# PortExpander.net
KiCad netlist of a schematic drawn in EAGLE
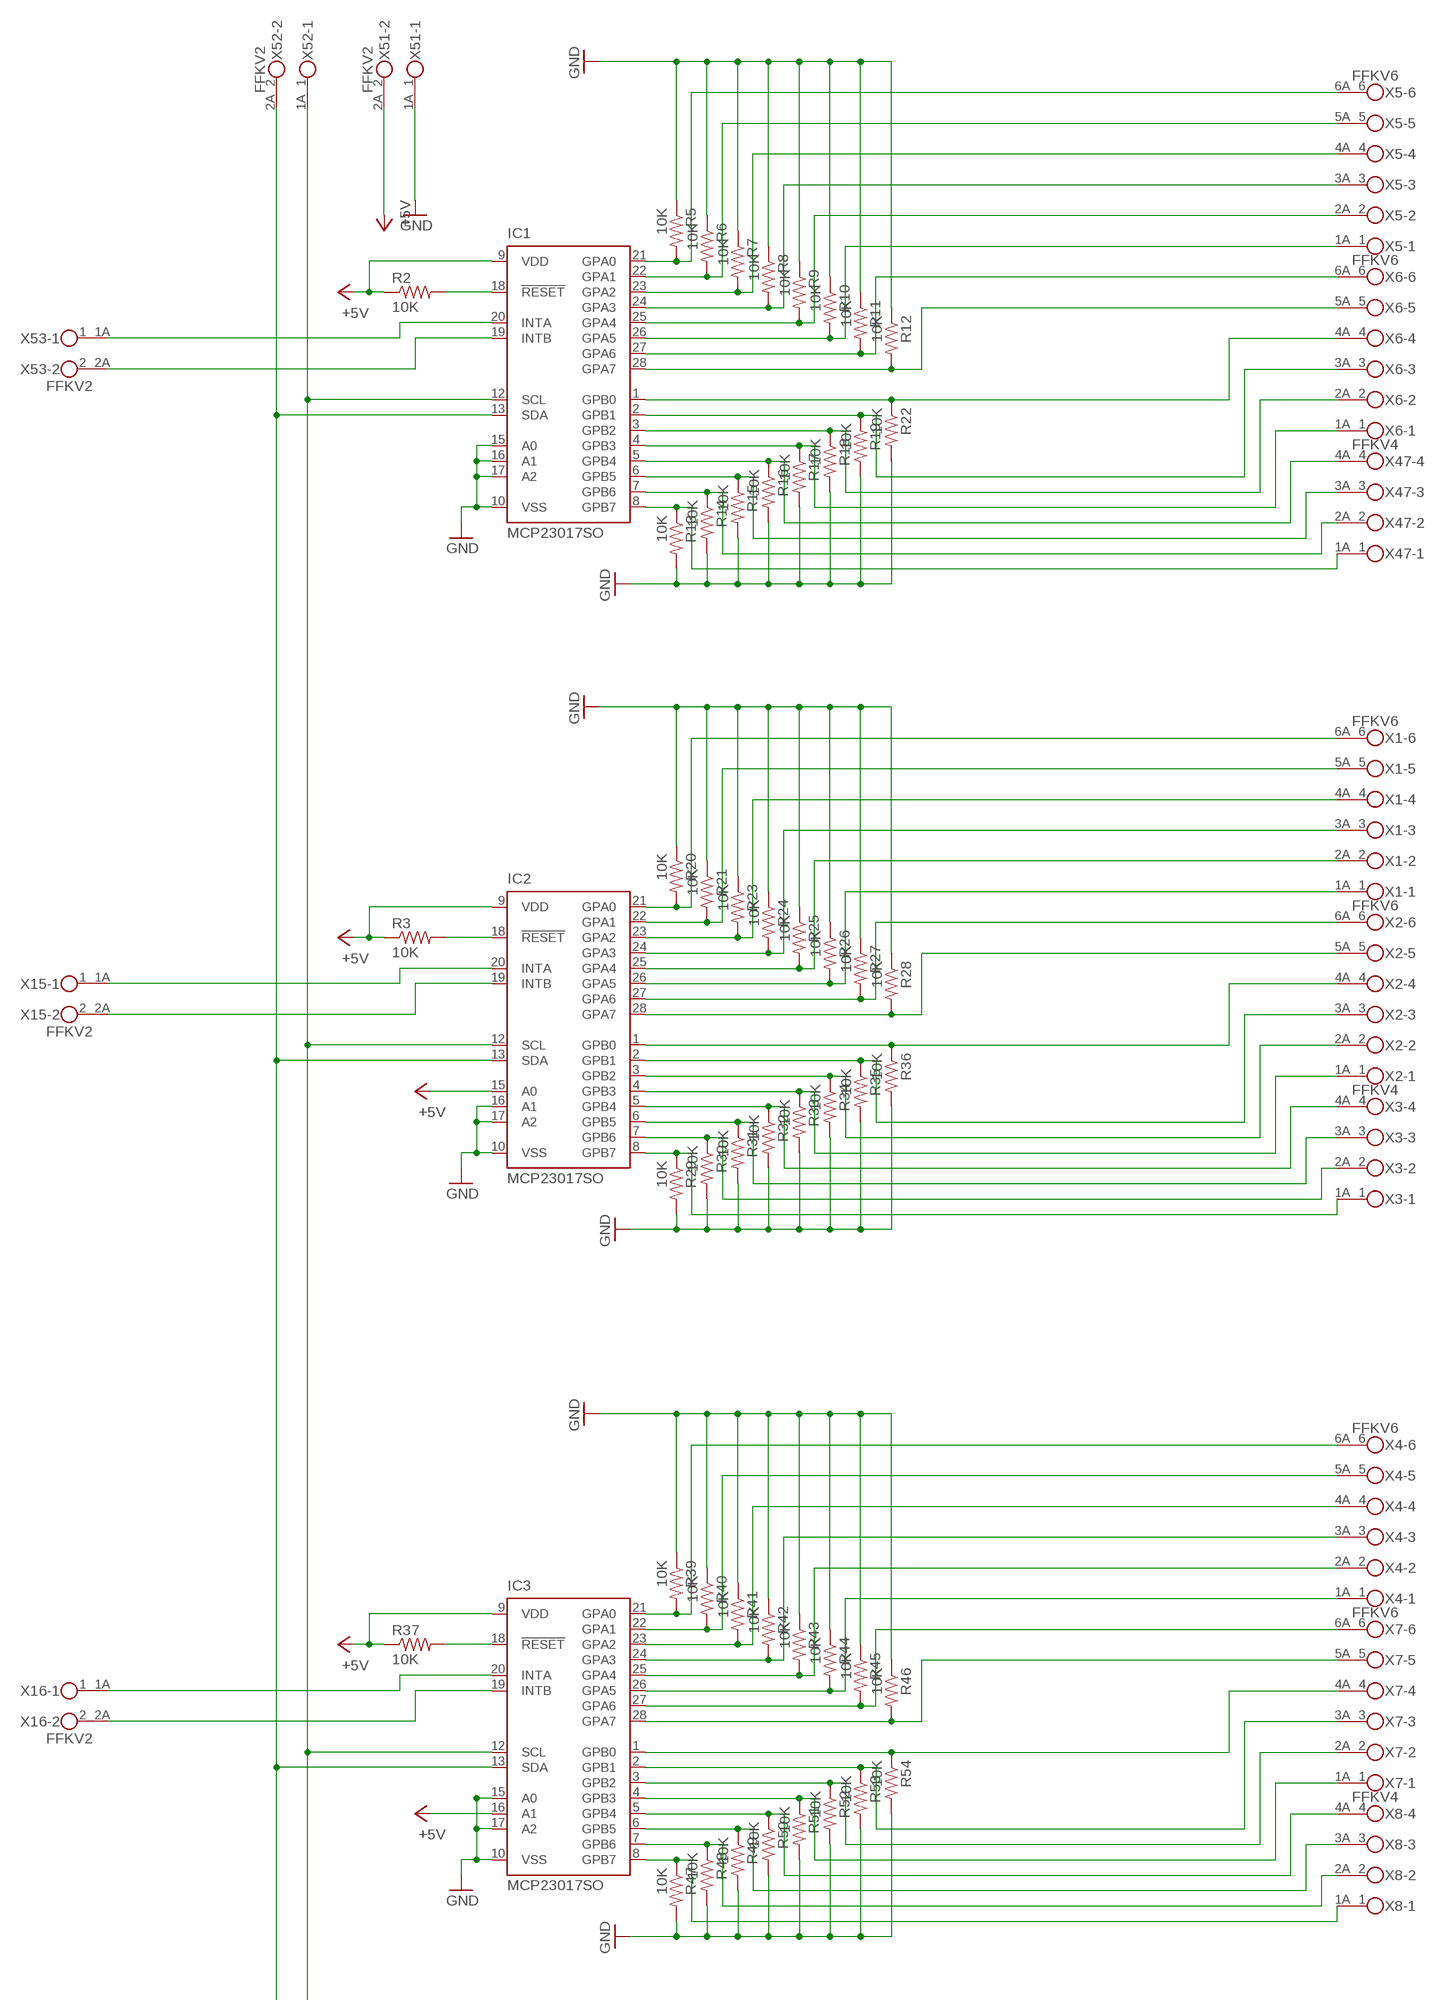
[diagram p0: schematic, sheet 1, part 1 of 2]
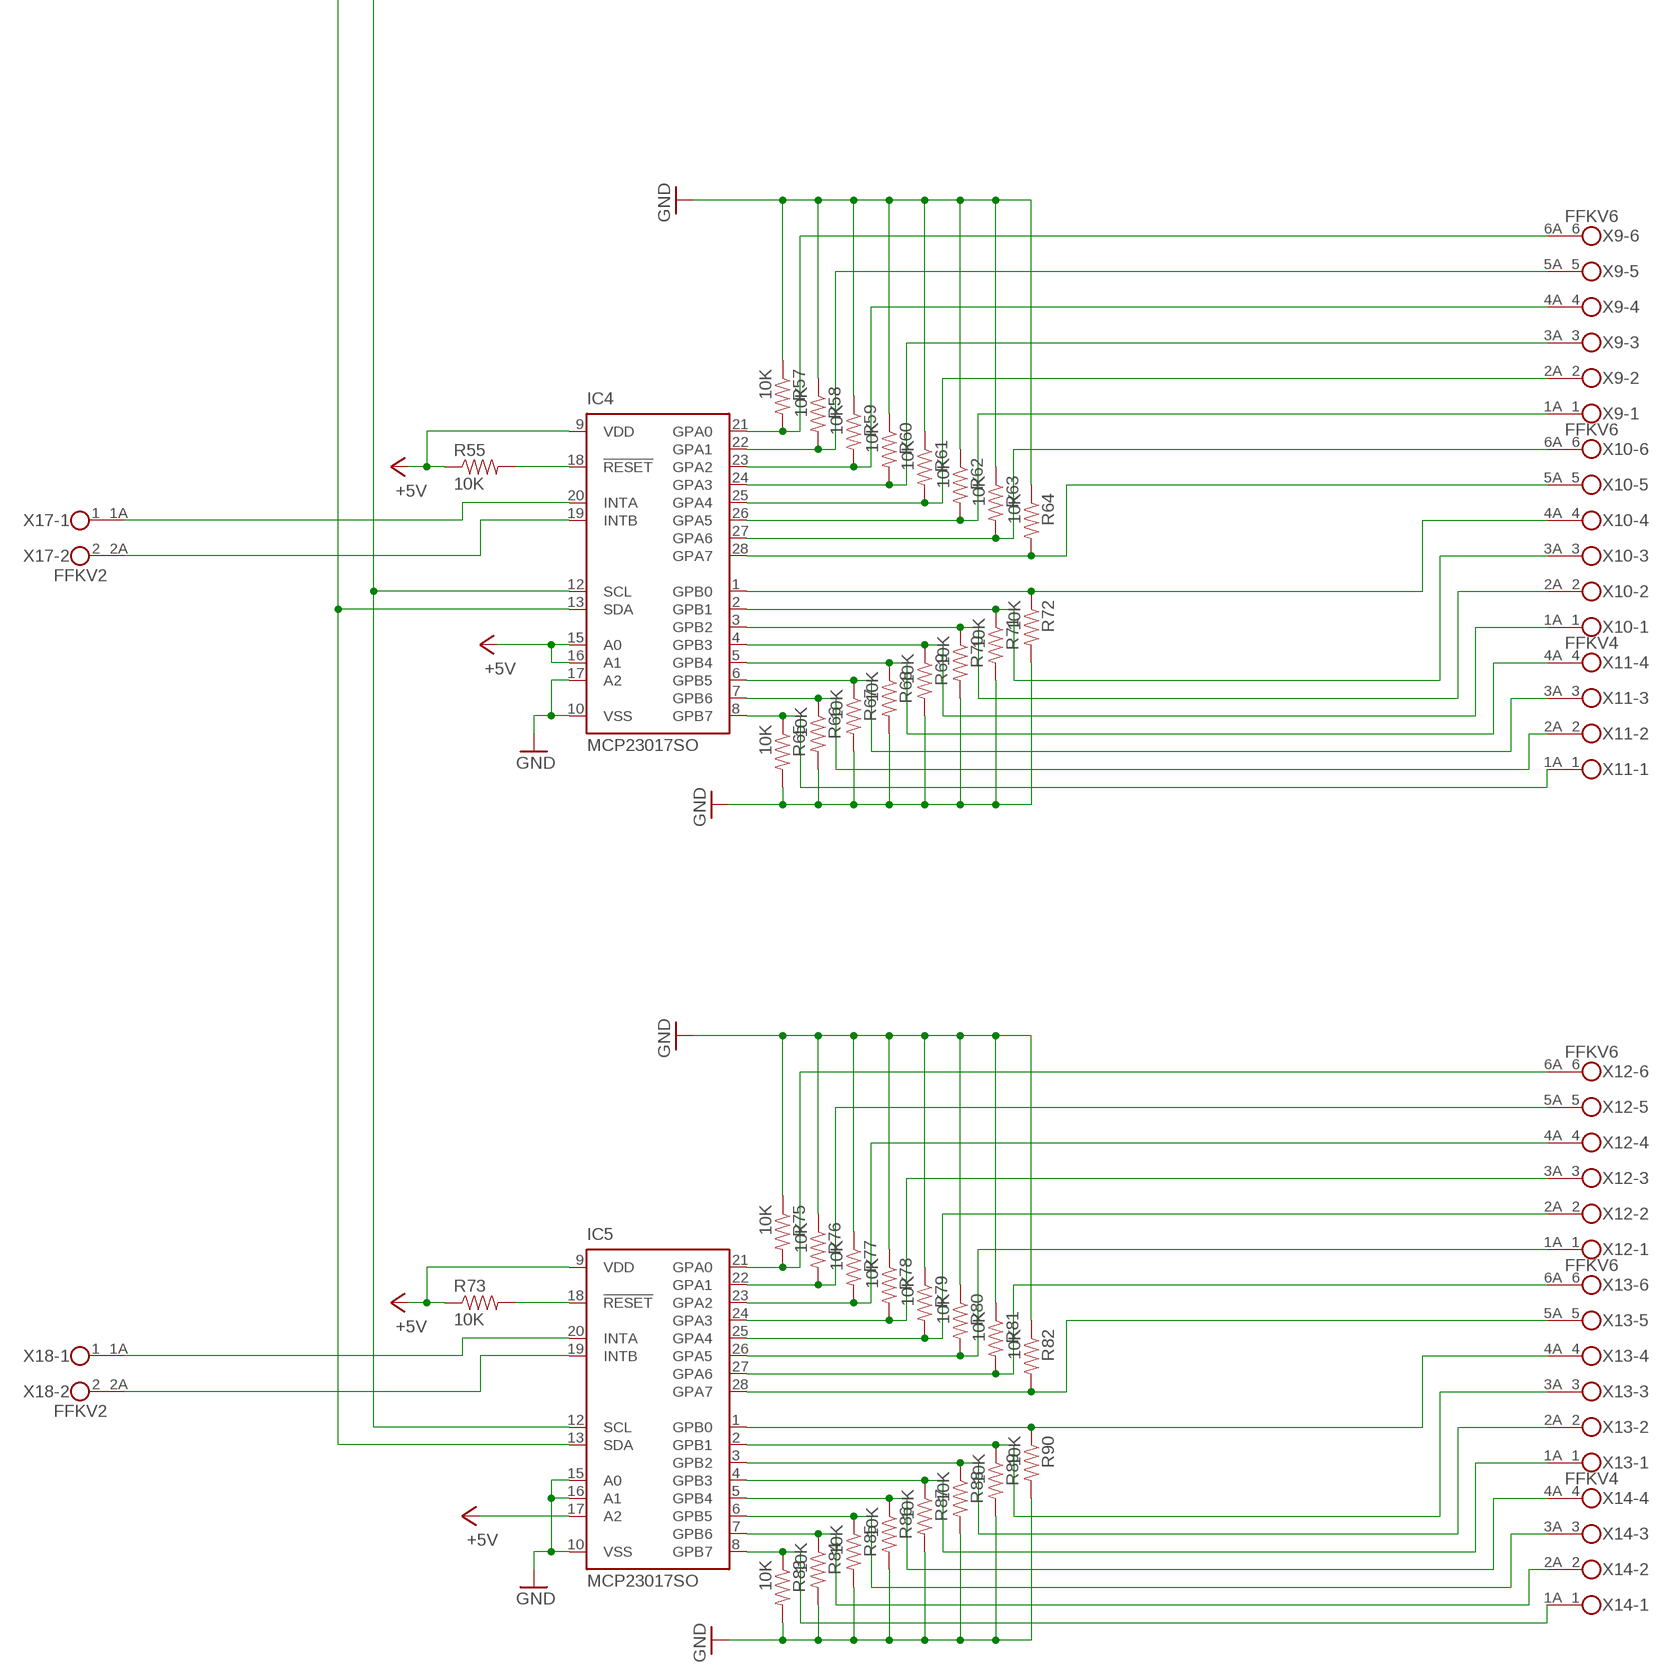
[diagram p1: schematic, sheet 1, part 2 of 2]

(export (version "E")
  (design (tool "Eeschema 10.0.6"))
  (components
    (comp (ref "IC1")
      (value "MCP23017SO")
      (footprint "eagle-import:SO28W")
      (fields (field (name "MF") "MICROCHIP") (field (name "MPN") "MCP23017-E/SO"))
      (libsource (lib "eagle-import") (part "MCP23017SO"))
    )
    (comp (ref "IC2")
      (value "MCP23017SO")
      (footprint "eagle-import:SO28W")
      (fields (field (name "MF") "MICROCHIP") (field (name "MPN") "MCP23017-E/SO"))
      (libsource (lib "eagle-import") (part "MCP23017SO"))
    )
    (comp (ref "IC3")
      (value "MCP23017SO")
      (footprint "eagle-import:SO28W")
      (fields (field (name "MF") "MICROCHIP") (field (name "MPN") "MCP23017-E/SO"))
      (libsource (lib "eagle-import") (part "MCP23017SO"))
    )
    (comp (ref "IC4")
      (value "MCP23017SO")
      (footprint "eagle-import:SO28W")
      (fields (field (name "MF") "MICROCHIP") (field (name "MPN") "MCP23017-E/SO"))
      (libsource (lib "eagle-import") (part "MCP23017SO"))
    )
    (comp (ref "IC5")
      (value "MCP23017SO")
      (footprint "eagle-import:SO28W")
      (fields (field (name "MF") "MICROCHIP") (field (name "MPN") "MCP23017-E/SO"))
      (libsource (lib "eagle-import") (part "MCP23017SO"))
    )
    (comp (ref "R2")
      (value "10K")
      (footprint "eagle-import:1206")
      (libsource (lib "eagle-import") (part "RESISTOR1206"))
    )
    (comp (ref "R3")
      (value "10K")
      (footprint "eagle-import:1206")
      (libsource (lib "eagle-import") (part "RESISTOR1206"))
    )
    (comp (ref "R5")
      (value "10K")
      (footprint "eagle-import:1206")
      (libsource (lib "eagle-import") (part "RESISTOR1206"))
    )
    (comp (ref "R6")
      (value "10K")
      (footprint "eagle-import:1206")
      (libsource (lib "eagle-import") (part "RESISTOR1206"))
    )
    (comp (ref "R7")
      (value "10K")
      (footprint "eagle-import:1206")
      (libsource (lib "eagle-import") (part "RESISTOR1206"))
    )
    (comp (ref "R8")
      (value "10K")
      (footprint "eagle-import:1206")
      (libsource (lib "eagle-import") (part "RESISTOR1206"))
    )
    (comp (ref "R9")
      (value "10K")
      (footprint "eagle-import:1206")
      (libsource (lib "eagle-import") (part "RESISTOR1206"))
    )
    (comp (ref "R10")
      (value "10K")
      (footprint "eagle-import:1206")
      (libsource (lib "eagle-import") (part "RESISTOR1206"))
    )
    (comp (ref "R11")
      (value "10K")
      (footprint "eagle-import:1206")
      (libsource (lib "eagle-import") (part "RESISTOR1206"))
    )
    (comp (ref "R12")
      (value "10K")
      (footprint "eagle-import:1206")
      (libsource (lib "eagle-import") (part "RESISTOR1206"))
    )
    (comp (ref "R13")
      (value "10K")
      (footprint "eagle-import:1206")
      (libsource (lib "eagle-import") (part "RESISTOR1206"))
    )
    (comp (ref "R14")
      (value "10K")
      (footprint "eagle-import:1206")
      (libsource (lib "eagle-import") (part "RESISTOR1206"))
    )
    (comp (ref "R15")
      (value "10K")
      (footprint "eagle-import:1206")
      (libsource (lib "eagle-import") (part "RESISTOR1206"))
    )
    (comp (ref "R16")
      (value "10K")
      (footprint "eagle-import:1206")
      (libsource (lib "eagle-import") (part "RESISTOR1206"))
    )
    (comp (ref "R17")
      (value "10K")
      (footprint "eagle-import:1206")
      (libsource (lib "eagle-import") (part "RESISTOR1206"))
    )
    (comp (ref "R18")
      (value "10K")
      (footprint "eagle-import:1206")
      (libsource (lib "eagle-import") (part "RESISTOR1206"))
    )
    (comp (ref "R19")
      (value "10K")
      (footprint "eagle-import:1206")
      (libsource (lib "eagle-import") (part "RESISTOR1206"))
    )
    (comp (ref "R20")
      (value "10K")
      (footprint "eagle-import:1206")
      (libsource (lib "eagle-import") (part "RESISTOR1206"))
    )
    (comp (ref "R21")
      (value "10K")
      (footprint "eagle-import:1206")
      (libsource (lib "eagle-import") (part "RESISTOR1206"))
    )
    (comp (ref "R22")
      (value "10K")
      (footprint "eagle-import:1206")
      (libsource (lib "eagle-import") (part "RESISTOR1206"))
    )
    (comp (ref "R23")
      (value "10K")
      (footprint "eagle-import:1206")
      (libsource (lib "eagle-import") (part "RESISTOR1206"))
    )
    (comp (ref "R24")
      (value "10K")
      (footprint "eagle-import:1206")
      (libsource (lib "eagle-import") (part "RESISTOR1206"))
    )
    (comp (ref "R25")
      (value "10K")
      (footprint "eagle-import:1206")
      (libsource (lib "eagle-import") (part "RESISTOR1206"))
    )
    (comp (ref "R26")
      (value "10K")
      (footprint "eagle-import:1206")
      (libsource (lib "eagle-import") (part "RESISTOR1206"))
    )
    (comp (ref "R27")
      (value "10K")
      (footprint "eagle-import:1206")
      (libsource (lib "eagle-import") (part "RESISTOR1206"))
    )
    (comp (ref "R28")
      (value "10K")
      (footprint "eagle-import:1206")
      (libsource (lib "eagle-import") (part "RESISTOR1206"))
    )
    (comp (ref "R29")
      (value "10K")
      (footprint "eagle-import:1206")
      (libsource (lib "eagle-import") (part "RESISTOR1206"))
    )
    (comp (ref "R30")
      (value "10K")
      (footprint "eagle-import:1206")
      (libsource (lib "eagle-import") (part "RESISTOR1206"))
    )
    (comp (ref "R31")
      (value "10K")
      (footprint "eagle-import:1206")
      (libsource (lib "eagle-import") (part "RESISTOR1206"))
    )
    (comp (ref "R32")
      (value "10K")
      (footprint "eagle-import:1206")
      (libsource (lib "eagle-import") (part "RESISTOR1206"))
    )
    (comp (ref "R33")
      (value "10K")
      (footprint "eagle-import:1206")
      (libsource (lib "eagle-import") (part "RESISTOR1206"))
    )
    (comp (ref "R34")
      (value "10K")
      (footprint "eagle-import:1206")
      (libsource (lib "eagle-import") (part "RESISTOR1206"))
    )
    (comp (ref "R35")
      (value "10K")
      (footprint "eagle-import:1206")
      (libsource (lib "eagle-import") (part "RESISTOR1206"))
    )
    (comp (ref "R36")
      (value "10K")
      (footprint "eagle-import:1206")
      (libsource (lib "eagle-import") (part "RESISTOR1206"))
    )
    (comp (ref "R37")
      (value "10K")
      (footprint "eagle-import:1206")
      (libsource (lib "eagle-import") (part "RESISTOR1206"))
    )
    (comp (ref "R39")
      (value "10K")
      (footprint "eagle-import:1206")
      (libsource (lib "eagle-import") (part "RESISTOR1206"))
    )
    (comp (ref "R40")
      (value "10K")
      (footprint "eagle-import:1206")
      (libsource (lib "eagle-import") (part "RESISTOR1206"))
    )
    (comp (ref "R41")
      (value "10K")
      (footprint "eagle-import:1206")
      (libsource (lib "eagle-import") (part "RESISTOR1206"))
    )
    (comp (ref "R42")
      (value "10K")
      (footprint "eagle-import:1206")
      (libsource (lib "eagle-import") (part "RESISTOR1206"))
    )
    (comp (ref "R43")
      (value "10K")
      (footprint "eagle-import:1206")
      (libsource (lib "eagle-import") (part "RESISTOR1206"))
    )
    (comp (ref "R44")
      (value "10K")
      (footprint "eagle-import:1206")
      (libsource (lib "eagle-import") (part "RESISTOR1206"))
    )
    (comp (ref "R45")
      (value "10K")
      (footprint "eagle-import:1206")
      (libsource (lib "eagle-import") (part "RESISTOR1206"))
    )
    (comp (ref "R46")
      (value "10K")
      (footprint "eagle-import:1206")
      (libsource (lib "eagle-import") (part "RESISTOR1206"))
    )
    (comp (ref "R47")
      (value "10K")
      (footprint "eagle-import:1206")
      (libsource (lib "eagle-import") (part "RESISTOR1206"))
    )
    (comp (ref "R48")
      (value "10K")
      (footprint "eagle-import:1206")
      (libsource (lib "eagle-import") (part "RESISTOR1206"))
    )
    (comp (ref "R49")
      (value "10K")
      (footprint "eagle-import:1206")
      (libsource (lib "eagle-import") (part "RESISTOR1206"))
    )
    (comp (ref "R50")
      (value "10K")
      (footprint "eagle-import:1206")
      (libsource (lib "eagle-import") (part "RESISTOR1206"))
    )
    (comp (ref "R51")
      (value "10K")
      (footprint "eagle-import:1206")
      (libsource (lib "eagle-import") (part "RESISTOR1206"))
    )
    (comp (ref "R52")
      (value "10K")
      (footprint "eagle-import:1206")
      (libsource (lib "eagle-import") (part "RESISTOR1206"))
    )
    (comp (ref "R53")
      (value "10K")
      (footprint "eagle-import:1206")
      (libsource (lib "eagle-import") (part "RESISTOR1206"))
    )
    (comp (ref "R54")
      (value "10K")
      (footprint "eagle-import:1206")
      (libsource (lib "eagle-import") (part "RESISTOR1206"))
    )
    (comp (ref "R55")
      (value "10K")
      (footprint "eagle-import:1206")
      (libsource (lib "eagle-import") (part "RESISTOR1206"))
    )
    (comp (ref "R57")
      (value "10K")
      (footprint "eagle-import:1206")
      (libsource (lib "eagle-import") (part "RESISTOR1206"))
    )
    (comp (ref "R58")
      (value "10K")
      (footprint "eagle-import:1206")
      (libsource (lib "eagle-import") (part "RESISTOR1206"))
    )
    (comp (ref "R59")
      (value "10K")
      (footprint "eagle-import:1206")
      (libsource (lib "eagle-import") (part "RESISTOR1206"))
    )
    (comp (ref "R60")
      (value "10K")
      (footprint "eagle-import:1206")
      (libsource (lib "eagle-import") (part "RESISTOR1206"))
    )
    (comp (ref "R61")
      (value "10K")
      (footprint "eagle-import:1206")
      (libsource (lib "eagle-import") (part "RESISTOR1206"))
    )
    (comp (ref "R62")
      (value "10K")
      (footprint "eagle-import:1206")
      (libsource (lib "eagle-import") (part "RESISTOR1206"))
    )
    (comp (ref "R63")
      (value "10K")
      (footprint "eagle-import:1206")
      (libsource (lib "eagle-import") (part "RESISTOR1206"))
    )
    (comp (ref "R64")
      (value "10K")
      (footprint "eagle-import:1206")
      (libsource (lib "eagle-import") (part "RESISTOR1206"))
    )
    (comp (ref "R65")
      (value "10K")
      (footprint "eagle-import:1206")
      (libsource (lib "eagle-import") (part "RESISTOR1206"))
    )
    (comp (ref "R66")
      (value "10K")
      (footprint "eagle-import:1206")
      (libsource (lib "eagle-import") (part "RESISTOR1206"))
    )
    (comp (ref "R67")
      (value "10K")
      (footprint "eagle-import:1206")
      (libsource (lib "eagle-import") (part "RESISTOR1206"))
    )
    (comp (ref "R68")
      (value "10K")
      (footprint "eagle-import:1206")
      (libsource (lib "eagle-import") (part "RESISTOR1206"))
    )
    (comp (ref "R69")
      (value "10K")
      (footprint "eagle-import:1206")
      (libsource (lib "eagle-import") (part "RESISTOR1206"))
    )
    (comp (ref "R70")
      (value "10K")
      (footprint "eagle-import:1206")
      (libsource (lib "eagle-import") (part "RESISTOR1206"))
    )
    (comp (ref "R71")
      (value "10K")
      (footprint "eagle-import:1206")
      (libsource (lib "eagle-import") (part "RESISTOR1206"))
    )
    (comp (ref "R72")
      (value "10K")
      (footprint "eagle-import:1206")
      (libsource (lib "eagle-import") (part "RESISTOR1206"))
    )
    (comp (ref "R73")
      (value "10K")
      (footprint "eagle-import:1206")
      (libsource (lib "eagle-import") (part "RESISTOR1206"))
    )
    (comp (ref "R75")
      (value "10K")
      (footprint "eagle-import:1206")
      (libsource (lib "eagle-import") (part "RESISTOR1206"))
    )
    (comp (ref "R76")
      (value "10K")
      (footprint "eagle-import:1206")
      (libsource (lib "eagle-import") (part "RESISTOR1206"))
    )
    (comp (ref "R77")
      (value "10K")
      (footprint "eagle-import:1206")
      (libsource (lib "eagle-import") (part "RESISTOR1206"))
    )
    (comp (ref "R78")
      (value "10K")
      (footprint "eagle-import:1206")
      (libsource (lib "eagle-import") (part "RESISTOR1206"))
    )
    (comp (ref "R79")
      (value "10K")
      (footprint "eagle-import:1206")
      (libsource (lib "eagle-import") (part "RESISTOR1206"))
    )
    (comp (ref "R80")
      (value "10K")
      (footprint "eagle-import:1206")
      (libsource (lib "eagle-import") (part "RESISTOR1206"))
    )
    (comp (ref "R81")
      (value "10K")
      (footprint "eagle-import:1206")
      (libsource (lib "eagle-import") (part "RESISTOR1206"))
    )
    (comp (ref "R82")
      (value "10K")
      (footprint "eagle-import:1206")
      (libsource (lib "eagle-import") (part "RESISTOR1206"))
    )
    (comp (ref "R83")
      (value "10K")
      (footprint "eagle-import:1206")
      (libsource (lib "eagle-import") (part "RESISTOR1206"))
    )
    (comp (ref "R84")
      (value "10K")
      (footprint "eagle-import:1206")
      (libsource (lib "eagle-import") (part "RESISTOR1206"))
    )
    (comp (ref "R85")
      (value "10K")
      (footprint "eagle-import:1206")
      (libsource (lib "eagle-import") (part "RESISTOR1206"))
    )
    (comp (ref "R86")
      (value "10K")
      (footprint "eagle-import:1206")
      (libsource (lib "eagle-import") (part "RESISTOR1206"))
    )
    (comp (ref "R87")
      (value "10K")
      (footprint "eagle-import:1206")
      (libsource (lib "eagle-import") (part "RESISTOR1206"))
    )
    (comp (ref "R88")
      (value "10K")
      (footprint "eagle-import:1206")
      (libsource (lib "eagle-import") (part "RESISTOR1206"))
    )
    (comp (ref "R89")
      (value "10K")
      (footprint "eagle-import:1206")
      (libsource (lib "eagle-import") (part "RESISTOR1206"))
    )
    (comp (ref "R90")
      (value "10K")
      (footprint "eagle-import:1206")
      (libsource (lib "eagle-import") (part "RESISTOR1206"))
    )
    (comp (ref "X1")
      (value "FFKV6")
      (footprint "eagle-import:FFKV6")
      (libsource (lib "eagle-import") (part "FFKV6"))
    )
    (comp (ref "X2")
      (value "FFKV6")
      (footprint "eagle-import:FFKV6")
      (libsource (lib "eagle-import") (part "FFKV6"))
    )
    (comp (ref "X3")
      (value "FFKV4")
      (footprint "eagle-import:FFKV4")
      (libsource (lib "eagle-import") (part "FFKV4"))
    )
    (comp (ref "X4")
      (value "FFKV6")
      (footprint "eagle-import:FFKV6")
      (libsource (lib "eagle-import") (part "FFKV6"))
    )
    (comp (ref "X5")
      (value "FFKV6")
      (footprint "eagle-import:FFKV6")
      (libsource (lib "eagle-import") (part "FFKV6"))
    )
    (comp (ref "X6")
      (value "FFKV6")
      (footprint "eagle-import:FFKV6")
      (libsource (lib "eagle-import") (part "FFKV6"))
    )
    (comp (ref "X7")
      (value "FFKV6")
      (footprint "eagle-import:FFKV6")
      (libsource (lib "eagle-import") (part "FFKV6"))
    )
    (comp (ref "X8")
      (value "FFKV4")
      (footprint "eagle-import:FFKV4")
      (libsource (lib "eagle-import") (part "FFKV4"))
    )
    (comp (ref "X9")
      (value "FFKV6")
      (footprint "eagle-import:FFKV6")
      (libsource (lib "eagle-import") (part "FFKV6"))
    )
    (comp (ref "X10")
      (value "FFKV6")
      (footprint "eagle-import:FFKV6")
      (libsource (lib "eagle-import") (part "FFKV6"))
    )
    (comp (ref "X11")
      (value "FFKV4")
      (footprint "eagle-import:FFKV4")
      (libsource (lib "eagle-import") (part "FFKV4"))
    )
    (comp (ref "X12")
      (value "FFKV6")
      (footprint "eagle-import:FFKV6")
      (libsource (lib "eagle-import") (part "FFKV6"))
    )
    (comp (ref "X13")
      (value "FFKV6")
      (footprint "eagle-import:FFKV6")
      (libsource (lib "eagle-import") (part "FFKV6"))
    )
    (comp (ref "X14")
      (value "FFKV4")
      (footprint "eagle-import:FFKV4")
      (libsource (lib "eagle-import") (part "FFKV4"))
    )
    (comp (ref "X15")
      (value "FFKV2")
      (footprint "eagle-import:FFKV2")
      (libsource (lib "eagle-import") (part "FFKV2"))
    )
    (comp (ref "X16")
      (value "FFKV2")
      (footprint "eagle-import:FFKV2")
      (libsource (lib "eagle-import") (part "FFKV2"))
    )
    (comp (ref "X17")
      (value "FFKV2")
      (footprint "eagle-import:FFKV2")
      (libsource (lib "eagle-import") (part "FFKV2"))
    )
    (comp (ref "X18")
      (value "FFKV2")
      (footprint "eagle-import:FFKV2")
      (libsource (lib "eagle-import") (part "FFKV2"))
    )
    (comp (ref "X47")
      (value "FFKV4")
      (footprint "eagle-import:FFKV4")
      (libsource (lib "eagle-import") (part "FFKV4"))
    )
    (comp (ref "X51")
      (value "FFKV2")
      (footprint "eagle-import:FFKV2")
      (libsource (lib "eagle-import") (part "FFKV2"))
    )
    (comp (ref "X52")
      (value "FFKV2")
      (footprint "eagle-import:FFKV2")
      (libsource (lib "eagle-import") (part "FFKV2"))
    )
    (comp (ref "X53")
      (value "FFKV2")
      (footprint "eagle-import:FFKV2")
      (libsource (lib "eagle-import") (part "FFKV2"))
    )
  )
  (nets
    (net (code "1") (name "+5V") (class "Default")
      (node (ref "IC1") (pin "9") (pinfunction "VDD_9") (pintype "power_in"))
      (node (ref "IC2") (pin "15") (pinfunction "A0_15") (pintype "input"))
      (node (ref "IC2") (pin "9") (pinfunction "VDD_9") (pintype "power_in"))
      (node (ref "IC3") (pin "16") (pinfunction "A1_16") (pintype "input"))
      (node (ref "IC3") (pin "9") (pinfunction "VDD_9") (pintype "power_in"))
      (node (ref "IC4") (pin "15") (pinfunction "A0_15") (pintype "input"))
      (node (ref "IC4") (pin "16") (pinfunction "A1_16") (pintype "input"))
      (node (ref "IC4") (pin "9") (pinfunction "VDD_9") (pintype "power_in"))
      (node (ref "IC5") (pin "17") (pinfunction "A2_17") (pintype "input"))
      (node (ref "IC5") (pin "9") (pinfunction "VDD_9") (pintype "power_in"))
      (node (ref "R2") (pin "1") (pinfunction "1_1") (pintype "passive"))
      (node (ref "R3") (pin "1") (pinfunction "1_1") (pintype "passive"))
      (node (ref "R37") (pin "1") (pinfunction "1_1") (pintype "passive"))
      (node (ref "R55") (pin "1") (pinfunction "1_1") (pintype "passive"))
      (node (ref "R73") (pin "1") (pinfunction "1_1") (pintype "passive"))
      (node (ref "X51") (pin "2A") (pinfunction "2_2A") (pintype "passive"))
    )
    (net (code "2") (name "GND") (class "Default")
      (node (ref "IC1") (pin "10") (pinfunction "VSS_10") (pintype "power_in"))
      (node (ref "IC1") (pin "15") (pinfunction "A0_15") (pintype "input"))
      (node (ref "IC1") (pin "16") (pinfunction "A1_16") (pintype "input"))
      (node (ref "IC1") (pin "17") (pinfunction "A2_17") (pintype "input"))
      (node (ref "IC2") (pin "10") (pinfunction "VSS_10") (pintype "power_in"))
      (node (ref "IC2") (pin "16") (pinfunction "A1_16") (pintype "input"))
      (node (ref "IC2") (pin "17") (pinfunction "A2_17") (pintype "input"))
      (node (ref "IC3") (pin "10") (pinfunction "VSS_10") (pintype "power_in"))
      (node (ref "IC3") (pin "15") (pinfunction "A0_15") (pintype "input"))
      (node (ref "IC3") (pin "17") (pinfunction "A2_17") (pintype "input"))
      (node (ref "IC4") (pin "10") (pinfunction "VSS_10") (pintype "power_in"))
      (node (ref "IC4") (pin "17") (pinfunction "A2_17") (pintype "input"))
      (node (ref "IC5") (pin "10") (pinfunction "VSS_10") (pintype "power_in"))
      (node (ref "IC5") (pin "15") (pinfunction "A0_15") (pintype "input"))
      (node (ref "IC5") (pin "16") (pinfunction "A1_16") (pintype "input"))
      (node (ref "R10") (pin "1") (pinfunction "1_1") (pintype "passive"))
      (node (ref "R11") (pin "1") (pinfunction "1_1") (pintype "passive"))
      (node (ref "R12") (pin "1") (pinfunction "1_1") (pintype "passive"))
      (node (ref "R13") (pin "2") (pinfunction "2_2") (pintype "passive"))
      (node (ref "R14") (pin "2") (pinfunction "2_2") (pintype "passive"))
      (node (ref "R15") (pin "2") (pinfunction "2_2") (pintype "passive"))
      (node (ref "R16") (pin "2") (pinfunction "2_2") (pintype "passive"))
      (node (ref "R17") (pin "2") (pinfunction "2_2") (pintype "passive"))
      (node (ref "R18") (pin "2") (pinfunction "2_2") (pintype "passive"))
      (node (ref "R19") (pin "2") (pinfunction "2_2") (pintype "passive"))
      (node (ref "R20") (pin "1") (pinfunction "1_1") (pintype "passive"))
      (node (ref "R21") (pin "1") (pinfunction "1_1") (pintype "passive"))
      (node (ref "R22") (pin "2") (pinfunction "2_2") (pintype "passive"))
      (node (ref "R23") (pin "1") (pinfunction "1_1") (pintype "passive"))
      (node (ref "R24") (pin "1") (pinfunction "1_1") (pintype "passive"))
      (node (ref "R25") (pin "1") (pinfunction "1_1") (pintype "passive"))
      (node (ref "R26") (pin "1") (pinfunction "1_1") (pintype "passive"))
      (node (ref "R27") (pin "1") (pinfunction "1_1") (pintype "passive"))
      (node (ref "R28") (pin "1") (pinfunction "1_1") (pintype "passive"))
      (node (ref "R29") (pin "2") (pinfunction "2_2") (pintype "passive"))
      (node (ref "R30") (pin "2") (pinfunction "2_2") (pintype "passive"))
      (node (ref "R31") (pin "2") (pinfunction "2_2") (pintype "passive"))
      (node (ref "R32") (pin "2") (pinfunction "2_2") (pintype "passive"))
      (node (ref "R33") (pin "2") (pinfunction "2_2") (pintype "passive"))
      (node (ref "R34") (pin "2") (pinfunction "2_2") (pintype "passive"))
      (node (ref "R35") (pin "2") (pinfunction "2_2") (pintype "passive"))
      (node (ref "R36") (pin "2") (pinfunction "2_2") (pintype "passive"))
      (node (ref "R39") (pin "1") (pinfunction "1_1") (pintype "passive"))
      (node (ref "R40") (pin "1") (pinfunction "1_1") (pintype "passive"))
      (node (ref "R41") (pin "1") (pinfunction "1_1") (pintype "passive"))
      (node (ref "R42") (pin "1") (pinfunction "1_1") (pintype "passive"))
      (node (ref "R43") (pin "1") (pinfunction "1_1") (pintype "passive"))
      (node (ref "R44") (pin "1") (pinfunction "1_1") (pintype "passive"))
      (node (ref "R45") (pin "1") (pinfunction "1_1") (pintype "passive"))
      (node (ref "R46") (pin "1") (pinfunction "1_1") (pintype "passive"))
      (node (ref "R47") (pin "2") (pinfunction "2_2") (pintype "passive"))
      (node (ref "R48") (pin "2") (pinfunction "2_2") (pintype "passive"))
      (node (ref "R49") (pin "2") (pinfunction "2_2") (pintype "passive"))
      (node (ref "R5") (pin "1") (pinfunction "1_1") (pintype "passive"))
      (node (ref "R50") (pin "2") (pinfunction "2_2") (pintype "passive"))
      (node (ref "R51") (pin "2") (pinfunction "2_2") (pintype "passive"))
      (node (ref "R52") (pin "2") (pinfunction "2_2") (pintype "passive"))
      (node (ref "R53") (pin "2") (pinfunction "2_2") (pintype "passive"))
      (node (ref "R54") (pin "2") (pinfunction "2_2") (pintype "passive"))
      (node (ref "R57") (pin "1") (pinfunction "1_1") (pintype "passive"))
      (node (ref "R58") (pin "1") (pinfunction "1_1") (pintype "passive"))
      (node (ref "R59") (pin "1") (pinfunction "1_1") (pintype "passive"))
      (node (ref "R6") (pin "1") (pinfunction "1_1") (pintype "passive"))
      (node (ref "R60") (pin "1") (pinfunction "1_1") (pintype "passive"))
      (node (ref "R61") (pin "1") (pinfunction "1_1") (pintype "passive"))
      (node (ref "R62") (pin "1") (pinfunction "1_1") (pintype "passive"))
      (node (ref "R63") (pin "1") (pinfunction "1_1") (pintype "passive"))
      (node (ref "R64") (pin "1") (pinfunction "1_1") (pintype "passive"))
      (node (ref "R65") (pin "2") (pinfunction "2_2") (pintype "passive"))
      (node (ref "R66") (pin "2") (pinfunction "2_2") (pintype "passive"))
      (node (ref "R67") (pin "2") (pinfunction "2_2") (pintype "passive"))
      (node (ref "R68") (pin "2") (pinfunction "2_2") (pintype "passive"))
      (node (ref "R69") (pin "2") (pinfunction "2_2") (pintype "passive"))
      (node (ref "R7") (pin "1") (pinfunction "1_1") (pintype "passive"))
      (node (ref "R70") (pin "2") (pinfunction "2_2") (pintype "passive"))
      (node (ref "R71") (pin "2") (pinfunction "2_2") (pintype "passive"))
      (node (ref "R72") (pin "2") (pinfunction "2_2") (pintype "passive"))
      (node (ref "R75") (pin "1") (pinfunction "1_1") (pintype "passive"))
      (node (ref "R76") (pin "1") (pinfunction "1_1") (pintype "passive"))
      (node (ref "R77") (pin "1") (pinfunction "1_1") (pintype "passive"))
      (node (ref "R78") (pin "1") (pinfunction "1_1") (pintype "passive"))
      (node (ref "R79") (pin "1") (pinfunction "1_1") (pintype "passive"))
      (node (ref "R8") (pin "1") (pinfunction "1_1") (pintype "passive"))
      (node (ref "R80") (pin "1") (pinfunction "1_1") (pintype "passive"))
      (node (ref "R81") (pin "1") (pinfunction "1_1") (pintype "passive"))
      (node (ref "R82") (pin "1") (pinfunction "1_1") (pintype "passive"))
      (node (ref "R83") (pin "2") (pinfunction "2_2") (pintype "passive"))
      (node (ref "R84") (pin "2") (pinfunction "2_2") (pintype "passive"))
      (node (ref "R85") (pin "2") (pinfunction "2_2") (pintype "passive"))
      (node (ref "R86") (pin "2") (pinfunction "2_2") (pintype "passive"))
      (node (ref "R87") (pin "2") (pinfunction "2_2") (pintype "passive"))
      (node (ref "R88") (pin "2") (pinfunction "2_2") (pintype "passive"))
      (node (ref "R89") (pin "2") (pinfunction "2_2") (pintype "passive"))
      (node (ref "R9") (pin "1") (pinfunction "1_1") (pintype "passive"))
      (node (ref "R90") (pin "2") (pinfunction "2_2") (pintype "passive"))
      (node (ref "X51") (pin "1A") (pinfunction "2_1A") (pintype "passive"))
    )
    (net (code "3") (name "Net-(IC1-GPA0)") (class "Default")
      (node (ref "IC1") (pin "21") (pinfunction "GPA0_21") (pintype "bidirectional"))
      (node (ref "R5") (pin "2") (pinfunction "2_2") (pintype "passive"))
      (node (ref "X5") (pin "6A") (pinfunction "2_6A") (pintype "passive"))
    )
    (net (code "4") (name "Net-(IC1-GPA1)") (class "Default")
      (node (ref "IC1") (pin "22") (pinfunction "GPA1_22") (pintype "bidirectional"))
      (node (ref "R6") (pin "2") (pinfunction "2_2") (pintype "passive"))
      (node (ref "X5") (pin "5A") (pinfunction "2_5A") (pintype "passive"))
    )
    (net (code "5") (name "Net-(IC1-GPA2)") (class "Default")
      (node (ref "IC1") (pin "23") (pinfunction "GPA2_23") (pintype "bidirectional"))
      (node (ref "R7") (pin "2") (pinfunction "2_2") (pintype "passive"))
      (node (ref "X5") (pin "4A") (pinfunction "2_4A") (pintype "passive"))
    )
    (net (code "6") (name "Net-(IC1-GPA3)") (class "Default")
      (node (ref "IC1") (pin "24") (pinfunction "GPA3_24") (pintype "bidirectional"))
      (node (ref "R8") (pin "2") (pinfunction "2_2") (pintype "passive"))
      (node (ref "X5") (pin "3A") (pinfunction "2_3A") (pintype "passive"))
    )
    (net (code "7") (name "Net-(IC1-GPA4)") (class "Default")
      (node (ref "IC1") (pin "25") (pinfunction "GPA4_25") (pintype "bidirectional"))
      (node (ref "R9") (pin "2") (pinfunction "2_2") (pintype "passive"))
      (node (ref "X5") (pin "2A") (pinfunction "2_2A") (pintype "passive"))
    )
    (net (code "8") (name "Net-(IC1-GPA5)") (class "Default")
      (node (ref "IC1") (pin "26") (pinfunction "GPA5_26") (pintype "bidirectional"))
      (node (ref "R10") (pin "2") (pinfunction "2_2") (pintype "passive"))
      (node (ref "X5") (pin "1A") (pinfunction "2_1A") (pintype "passive"))
    )
    (net (code "9") (name "Net-(IC1-GPA6)") (class "Default")
      (node (ref "IC1") (pin "27") (pinfunction "GPA6_27") (pintype "bidirectional"))
      (node (ref "R11") (pin "2") (pinfunction "2_2") (pintype "passive"))
      (node (ref "X6") (pin "6A") (pinfunction "2_6A") (pintype "passive"))
    )
    (net (code "10") (name "Net-(IC1-GPA7)") (class "Default")
      (node (ref "IC1") (pin "28") (pinfunction "GPA7_28") (pintype "bidirectional"))
      (node (ref "R12") (pin "2") (pinfunction "2_2") (pintype "passive"))
      (node (ref "X6") (pin "5A") (pinfunction "2_5A") (pintype "passive"))
    )
    (net (code "11") (name "Net-(IC1-GPB0)") (class "Default")
      (node (ref "IC1") (pin "1") (pinfunction "GPB0_1") (pintype "bidirectional"))
      (node (ref "R22") (pin "1") (pinfunction "1_1") (pintype "passive"))
      (node (ref "X6") (pin "4A") (pinfunction "2_4A") (pintype "passive"))
    )
    (net (code "12") (name "Net-(IC1-GPB1)") (class "Default")
      (node (ref "IC1") (pin "2") (pinfunction "GPB1_2") (pintype "bidirectional"))
      (node (ref "R19") (pin "1") (pinfunction "1_1") (pintype "passive"))
      (node (ref "X6") (pin "3A") (pinfunction "2_3A") (pintype "passive"))
    )
    (net (code "13") (name "Net-(IC1-GPB2)") (class "Default")
      (node (ref "IC1") (pin "3") (pinfunction "GPB2_3") (pintype "bidirectional"))
      (node (ref "R18") (pin "1") (pinfunction "1_1") (pintype "passive"))
      (node (ref "X6") (pin "2A") (pinfunction "2_2A") (pintype "passive"))
    )
    (net (code "14") (name "Net-(IC1-GPB3)") (class "Default")
      (node (ref "IC1") (pin "4") (pinfunction "GPB3_4") (pintype "bidirectional"))
      (node (ref "R17") (pin "1") (pinfunction "1_1") (pintype "passive"))
      (node (ref "X6") (pin "1A") (pinfunction "2_1A") (pintype "passive"))
    )
    (net (code "15") (name "Net-(IC1-GPB4)") (class "Default")
      (node (ref "IC1") (pin "5") (pinfunction "GPB4_5") (pintype "bidirectional"))
      (node (ref "R16") (pin "1") (pinfunction "1_1") (pintype "passive"))
      (node (ref "X47") (pin "4A") (pinfunction "2_4A") (pintype "passive"))
    )
    (net (code "16") (name "Net-(IC1-GPB5)") (class "Default")
      (node (ref "IC1") (pin "6") (pinfunction "GPB5_6") (pintype "bidirectional"))
      (node (ref "R15") (pin "1") (pinfunction "1_1") (pintype "passive"))
      (node (ref "X47") (pin "3A") (pinfunction "2_3A") (pintype "passive"))
    )
    (net (code "17") (name "Net-(IC1-GPB6)") (class "Default")
      (node (ref "IC1") (pin "7") (pinfunction "GPB6_7") (pintype "bidirectional"))
      (node (ref "R14") (pin "1") (pinfunction "1_1") (pintype "passive"))
      (node (ref "X47") (pin "2A") (pinfunction "2_2A") (pintype "passive"))
    )
    (net (code "18") (name "Net-(IC1-GPB7)") (class "Default")
      (node (ref "IC1") (pin "8") (pinfunction "GPB7_8") (pintype "bidirectional"))
      (node (ref "R13") (pin "1") (pinfunction "1_1") (pintype "passive"))
      (node (ref "X47") (pin "1A") (pinfunction "2_1A") (pintype "passive"))
    )
    (net (code "19") (name "Net-(IC1-INTA)") (class "Default")
      (node (ref "IC1") (pin "20") (pinfunction "INTA_20") (pintype "output"))
      (node (ref "X53") (pin "1A") (pinfunction "2_1A") (pintype "passive"))
    )
    (net (code "20") (name "Net-(IC1-INTB)") (class "Default")
      (node (ref "IC1") (pin "19") (pinfunction "INTB_19") (pintype "output"))
      (node (ref "X53") (pin "2A") (pinfunction "2_2A") (pintype "passive"))
    )
    (net (code "21") (name "Net-(IC1-SCL)") (class "Default")
      (node (ref "IC1") (pin "12") (pinfunction "SCL_12") (pintype "input"))
      (node (ref "IC2") (pin "12") (pinfunction "SCL_12") (pintype "input"))
      (node (ref "IC3") (pin "12") (pinfunction "SCL_12") (pintype "input"))
      (node (ref "IC4") (pin "12") (pinfunction "SCL_12") (pintype "input"))
      (node (ref "IC5") (pin "12") (pinfunction "SCL_12") (pintype "input"))
      (node (ref "X52") (pin "1A") (pinfunction "2_1A") (pintype "passive"))
    )
    (net (code "22") (name "Net-(IC1-SDA)") (class "Default")
      (node (ref "IC1") (pin "13") (pinfunction "SDA_13") (pintype "bidirectional"))
      (node (ref "IC2") (pin "13") (pinfunction "SDA_13") (pintype "bidirectional"))
      (node (ref "IC3") (pin "13") (pinfunction "SDA_13") (pintype "bidirectional"))
      (node (ref "IC4") (pin "13") (pinfunction "SDA_13") (pintype "bidirectional"))
      (node (ref "IC5") (pin "13") (pinfunction "SDA_13") (pintype "bidirectional"))
      (node (ref "X52") (pin "2A") (pinfunction "2_2A") (pintype "passive"))
    )
    (net (code "23") (name "Net-(IC1-~{RESET})") (class "Default")
      (node (ref "IC1") (pin "18") (pinfunction "~{RESET}_18") (pintype "input"))
      (node (ref "R2") (pin "2") (pinfunction "2_2") (pintype "passive"))
    )
    (net (code "24") (name "Net-(IC2-GPA0)") (class "Default")
      (node (ref "IC2") (pin "21") (pinfunction "GPA0_21") (pintype "bidirectional"))
      (node (ref "R20") (pin "2") (pinfunction "2_2") (pintype "passive"))
      (node (ref "X1") (pin "6A") (pinfunction "2_6A") (pintype "passive"))
    )
    (net (code "25") (name "Net-(IC2-GPA1)") (class "Default")
      (node (ref "IC2") (pin "22") (pinfunction "GPA1_22") (pintype "bidirectional"))
      (node (ref "R21") (pin "2") (pinfunction "2_2") (pintype "passive"))
      (node (ref "X1") (pin "5A") (pinfunction "2_5A") (pintype "passive"))
    )
    (net (code "26") (name "Net-(IC2-GPA2)") (class "Default")
      (node (ref "IC2") (pin "23") (pinfunction "GPA2_23") (pintype "bidirectional"))
      (node (ref "R23") (pin "2") (pinfunction "2_2") (pintype "passive"))
      (node (ref "X1") (pin "4A") (pinfunction "2_4A") (pintype "passive"))
    )
    (net (code "27") (name "Net-(IC2-GPA3)") (class "Default")
      (node (ref "IC2") (pin "24") (pinfunction "GPA3_24") (pintype "bidirectional"))
      (node (ref "R24") (pin "2") (pinfunction "2_2") (pintype "passive"))
      (node (ref "X1") (pin "3A") (pinfunction "2_3A") (pintype "passive"))
    )
    (net (code "28") (name "Net-(IC2-GPA4)") (class "Default")
      (node (ref "IC2") (pin "25") (pinfunction "GPA4_25") (pintype "bidirectional"))
      (node (ref "R25") (pin "2") (pinfunction "2_2") (pintype "passive"))
      (node (ref "X1") (pin "2A") (pinfunction "2_2A") (pintype "passive"))
    )
    (net (code "29") (name "Net-(IC2-GPA5)") (class "Default")
      (node (ref "IC2") (pin "26") (pinfunction "GPA5_26") (pintype "bidirectional"))
      (node (ref "R26") (pin "2") (pinfunction "2_2") (pintype "passive"))
      (node (ref "X1") (pin "1A") (pinfunction "2_1A") (pintype "passive"))
    )
    (net (code "30") (name "Net-(IC2-GPA6)") (class "Default")
      (node (ref "IC2") (pin "27") (pinfunction "GPA6_27") (pintype "bidirectional"))
      (node (ref "R27") (pin "2") (pinfunction "2_2") (pintype "passive"))
      (node (ref "X2") (pin "6A") (pinfunction "2_6A") (pintype "passive"))
    )
    (net (code "31") (name "Net-(IC2-GPA7)") (class "Default")
      (node (ref "IC2") (pin "28") (pinfunction "GPA7_28") (pintype "bidirectional"))
      (node (ref "R28") (pin "2") (pinfunction "2_2") (pintype "passive"))
      (node (ref "X2") (pin "5A") (pinfunction "2_5A") (pintype "passive"))
    )
    (net (code "32") (name "Net-(IC2-GPB0)") (class "Default")
      (node (ref "IC2") (pin "1") (pinfunction "GPB0_1") (pintype "bidirectional"))
      (node (ref "R36") (pin "1") (pinfunction "1_1") (pintype "passive"))
      (node (ref "X2") (pin "4A") (pinfunction "2_4A") (pintype "passive"))
    )
    (net (code "33") (name "Net-(IC2-GPB1)") (class "Default")
      (node (ref "IC2") (pin "2") (pinfunction "GPB1_2") (pintype "bidirectional"))
      (node (ref "R35") (pin "1") (pinfunction "1_1") (pintype "passive"))
      (node (ref "X2") (pin "3A") (pinfunction "2_3A") (pintype "passive"))
    )
    (net (code "34") (name "Net-(IC2-GPB2)") (class "Default")
      (node (ref "IC2") (pin "3") (pinfunction "GPB2_3") (pintype "bidirectional"))
      (node (ref "R34") (pin "1") (pinfunction "1_1") (pintype "passive"))
      (node (ref "X2") (pin "2A") (pinfunction "2_2A") (pintype "passive"))
    )
    (net (code "35") (name "Net-(IC2-GPB3)") (class "Default")
      (node (ref "IC2") (pin "4") (pinfunction "GPB3_4") (pintype "bidirectional"))
      (node (ref "R33") (pin "1") (pinfunction "1_1") (pintype "passive"))
      (node (ref "X2") (pin "1A") (pinfunction "2_1A") (pintype "passive"))
    )
    (net (code "36") (name "Net-(IC2-GPB4)") (class "Default")
      (node (ref "IC2") (pin "5") (pinfunction "GPB4_5") (pintype "bidirectional"))
      (node (ref "R32") (pin "1") (pinfunction "1_1") (pintype "passive"))
      (node (ref "X3") (pin "4A") (pinfunction "2_4A") (pintype "passive"))
    )
    (net (code "37") (name "Net-(IC2-GPB5)") (class "Default")
      (node (ref "IC2") (pin "6") (pinfunction "GPB5_6") (pintype "bidirectional"))
      (node (ref "R31") (pin "1") (pinfunction "1_1") (pintype "passive"))
      (node (ref "X3") (pin "3A") (pinfunction "2_3A") (pintype "passive"))
    )
    (net (code "38") (name "Net-(IC2-GPB6)") (class "Default")
      (node (ref "IC2") (pin "7") (pinfunction "GPB6_7") (pintype "bidirectional"))
      (node (ref "R30") (pin "1") (pinfunction "1_1") (pintype "passive"))
      (node (ref "X3") (pin "2A") (pinfunction "2_2A") (pintype "passive"))
    )
    (net (code "39") (name "Net-(IC2-GPB7)") (class "Default")
      (node (ref "IC2") (pin "8") (pinfunction "GPB7_8") (pintype "bidirectional"))
      (node (ref "R29") (pin "1") (pinfunction "1_1") (pintype "passive"))
      (node (ref "X3") (pin "1A") (pinfunction "2_1A") (pintype "passive"))
    )
    (net (code "40") (name "Net-(IC2-INTA)") (class "Default")
      (node (ref "IC2") (pin "20") (pinfunction "INTA_20") (pintype "output"))
      (node (ref "X15") (pin "1A") (pinfunction "2_1A") (pintype "passive"))
    )
    (net (code "41") (name "Net-(IC2-INTB)") (class "Default")
      (node (ref "IC2") (pin "19") (pinfunction "INTB_19") (pintype "output"))
      (node (ref "X15") (pin "2A") (pinfunction "2_2A") (pintype "passive"))
    )
    (net (code "42") (name "Net-(IC2-~{RESET})") (class "Default")
      (node (ref "IC2") (pin "18") (pinfunction "~{RESET}_18") (pintype "input"))
      (node (ref "R3") (pin "2") (pinfunction "2_2") (pintype "passive"))
    )
    (net (code "43") (name "Net-(IC3-GPA0)") (class "Default")
      (node (ref "IC3") (pin "21") (pinfunction "GPA0_21") (pintype "bidirectional"))
      (node (ref "R39") (pin "2") (pinfunction "2_2") (pintype "passive"))
      (node (ref "X4") (pin "6A") (pinfunction "2_6A") (pintype "passive"))
    )
    (net (code "44") (name "Net-(IC3-GPA1)") (class "Default")
      (node (ref "IC3") (pin "22") (pinfunction "GPA1_22") (pintype "bidirectional"))
      (node (ref "R40") (pin "2") (pinfunction "2_2") (pintype "passive"))
      (node (ref "X4") (pin "5A") (pinfunction "2_5A") (pintype "passive"))
    )
    (net (code "45") (name "Net-(IC3-GPA2)") (class "Default")
      (node (ref "IC3") (pin "23") (pinfunction "GPA2_23") (pintype "bidirectional"))
      (node (ref "R41") (pin "2") (pinfunction "2_2") (pintype "passive"))
      (node (ref "X4") (pin "4A") (pinfunction "2_4A") (pintype "passive"))
    )
    (net (code "46") (name "Net-(IC3-GPA3)") (class "Default")
      (node (ref "IC3") (pin "24") (pinfunction "GPA3_24") (pintype "bidirectional"))
      (node (ref "R42") (pin "2") (pinfunction "2_2") (pintype "passive"))
      (node (ref "X4") (pin "3A") (pinfunction "2_3A") (pintype "passive"))
    )
    (net (code "47") (name "Net-(IC3-GPA4)") (class "Default")
      (node (ref "IC3") (pin "25") (pinfunction "GPA4_25") (pintype "bidirectional"))
      (node (ref "R43") (pin "2") (pinfunction "2_2") (pintype "passive"))
      (node (ref "X4") (pin "2A") (pinfunction "2_2A") (pintype "passive"))
    )
    (net (code "48") (name "Net-(IC3-GPA5)") (class "Default")
      (node (ref "IC3") (pin "26") (pinfunction "GPA5_26") (pintype "bidirectional"))
      (node (ref "R44") (pin "2") (pinfunction "2_2") (pintype "passive"))
      (node (ref "X4") (pin "1A") (pinfunction "2_1A") (pintype "passive"))
    )
    (net (code "49") (name "Net-(IC3-GPA6)") (class "Default")
      (node (ref "IC3") (pin "27") (pinfunction "GPA6_27") (pintype "bidirectional"))
      (node (ref "R45") (pin "2") (pinfunction "2_2") (pintype "passive"))
      (node (ref "X7") (pin "6A") (pinfunction "2_6A") (pintype "passive"))
    )
    (net (code "50") (name "Net-(IC3-GPA7)") (class "Default")
      (node (ref "IC3") (pin "28") (pinfunction "GPA7_28") (pintype "bidirectional"))
      (node (ref "R46") (pin "2") (pinfunction "2_2") (pintype "passive"))
      (node (ref "X7") (pin "5A") (pinfunction "2_5A") (pintype "passive"))
    )
    (net (code "51") (name "Net-(IC3-GPB0)") (class "Default")
      (node (ref "IC3") (pin "1") (pinfunction "GPB0_1") (pintype "bidirectional"))
      (node (ref "R54") (pin "1") (pinfunction "1_1") (pintype "passive"))
      (node (ref "X7") (pin "4A") (pinfunction "2_4A") (pintype "passive"))
    )
    (net (code "52") (name "Net-(IC3-GPB1)") (class "Default")
      (node (ref "IC3") (pin "2") (pinfunction "GPB1_2") (pintype "bidirectional"))
      (node (ref "R53") (pin "1") (pinfunction "1_1") (pintype "passive"))
      (node (ref "X7") (pin "3A") (pinfunction "2_3A") (pintype "passive"))
    )
    (net (code "53") (name "Net-(IC3-GPB2)") (class "Default")
      (node (ref "IC3") (pin "3") (pinfunction "GPB2_3") (pintype "bidirectional"))
      (node (ref "R52") (pin "1") (pinfunction "1_1") (pintype "passive"))
      (node (ref "X7") (pin "2A") (pinfunction "2_2A") (pintype "passive"))
    )
    (net (code "54") (name "Net-(IC3-GPB3)") (class "Default")
      (node (ref "IC3") (pin "4") (pinfunction "GPB3_4") (pintype "bidirectional"))
      (node (ref "R51") (pin "1") (pinfunction "1_1") (pintype "passive"))
      (node (ref "X7") (pin "1A") (pinfunction "2_1A") (pintype "passive"))
    )
    (net (code "55") (name "Net-(IC3-GPB4)") (class "Default")
      (node (ref "IC3") (pin "5") (pinfunction "GPB4_5") (pintype "bidirectional"))
      (node (ref "R50") (pin "1") (pinfunction "1_1") (pintype "passive"))
      (node (ref "X8") (pin "4A") (pinfunction "2_4A") (pintype "passive"))
    )
    (net (code "56") (name "Net-(IC3-GPB5)") (class "Default")
      (node (ref "IC3") (pin "6") (pinfunction "GPB5_6") (pintype "bidirectional"))
      (node (ref "R49") (pin "1") (pinfunction "1_1") (pintype "passive"))
      (node (ref "X8") (pin "3A") (pinfunction "2_3A") (pintype "passive"))
    )
    (net (code "57") (name "Net-(IC3-GPB6)") (class "Default")
      (node (ref "IC3") (pin "7") (pinfunction "GPB6_7") (pintype "bidirectional"))
      (node (ref "R48") (pin "1") (pinfunction "1_1") (pintype "passive"))
      (node (ref "X8") (pin "2A") (pinfunction "2_2A") (pintype "passive"))
    )
    (net (code "58") (name "Net-(IC3-GPB7)") (class "Default")
      (node (ref "IC3") (pin "8") (pinfunction "GPB7_8") (pintype "bidirectional"))
      (node (ref "R47") (pin "1") (pinfunction "1_1") (pintype "passive"))
      (node (ref "X8") (pin "1A") (pinfunction "2_1A") (pintype "passive"))
    )
    (net (code "59") (name "Net-(IC3-INTA)") (class "Default")
      (node (ref "IC3") (pin "20") (pinfunction "INTA_20") (pintype "output"))
      (node (ref "X16") (pin "1A") (pinfunction "2_1A") (pintype "passive"))
    )
    (net (code "60") (name "Net-(IC3-INTB)") (class "Default")
      (node (ref "IC3") (pin "19") (pinfunction "INTB_19") (pintype "output"))
      (node (ref "X16") (pin "2A") (pinfunction "2_2A") (pintype "passive"))
    )
    (net (code "61") (name "Net-(IC3-~{RESET})") (class "Default")
      (node (ref "IC3") (pin "18") (pinfunction "~{RESET}_18") (pintype "input"))
      (node (ref "R37") (pin "2") (pinfunction "2_2") (pintype "passive"))
    )
    (net (code "62") (name "Net-(IC4-GPA0)") (class "Default")
      (node (ref "IC4") (pin "21") (pinfunction "GPA0_21") (pintype "bidirectional"))
      (node (ref "R57") (pin "2") (pinfunction "2_2") (pintype "passive"))
      (node (ref "X9") (pin "6A") (pinfunction "2_6A") (pintype "passive"))
    )
    (net (code "63") (name "Net-(IC4-GPA1)") (class "Default")
      (node (ref "IC4") (pin "22") (pinfunction "GPA1_22") (pintype "bidirectional"))
      (node (ref "R58") (pin "2") (pinfunction "2_2") (pintype "passive"))
      (node (ref "X9") (pin "5A") (pinfunction "2_5A") (pintype "passive"))
    )
    (net (code "64") (name "Net-(IC4-GPA2)") (class "Default")
      (node (ref "IC4") (pin "23") (pinfunction "GPA2_23") (pintype "bidirectional"))
      (node (ref "R59") (pin "2") (pinfunction "2_2") (pintype "passive"))
      (node (ref "X9") (pin "4A") (pinfunction "2_4A") (pintype "passive"))
    )
    (net (code "65") (name "Net-(IC4-GPA3)") (class "Default")
      (node (ref "IC4") (pin "24") (pinfunction "GPA3_24") (pintype "bidirectional"))
      (node (ref "R60") (pin "2") (pinfunction "2_2") (pintype "passive"))
      (node (ref "X9") (pin "3A") (pinfunction "2_3A") (pintype "passive"))
    )
    (net (code "66") (name "Net-(IC4-GPA4)") (class "Default")
      (node (ref "IC4") (pin "25") (pinfunction "GPA4_25") (pintype "bidirectional"))
      (node (ref "R61") (pin "2") (pinfunction "2_2") (pintype "passive"))
      (node (ref "X9") (pin "2A") (pinfunction "2_2A") (pintype "passive"))
    )
    (net (code "67") (name "Net-(IC4-GPA5)") (class "Default")
      (node (ref "IC4") (pin "26") (pinfunction "GPA5_26") (pintype "bidirectional"))
      (node (ref "R62") (pin "2") (pinfunction "2_2") (pintype "passive"))
      (node (ref "X9") (pin "1A") (pinfunction "2_1A") (pintype "passive"))
    )
    (net (code "68") (name "Net-(IC4-GPA6)") (class "Default")
      (node (ref "IC4") (pin "27") (pinfunction "GPA6_27") (pintype "bidirectional"))
      (node (ref "R63") (pin "2") (pinfunction "2_2") (pintype "passive"))
      (node (ref "X10") (pin "6A") (pinfunction "2_6A") (pintype "passive"))
    )
    (net (code "69") (name "Net-(IC4-GPA7)") (class "Default")
      (node (ref "IC4") (pin "28") (pinfunction "GPA7_28") (pintype "bidirectional"))
      (node (ref "R64") (pin "2") (pinfunction "2_2") (pintype "passive"))
      (node (ref "X10") (pin "5A") (pinfunction "2_5A") (pintype "passive"))
    )
    (net (code "70") (name "Net-(IC4-GPB0)") (class "Default")
      (node (ref "IC4") (pin "1") (pinfunction "GPB0_1") (pintype "bidirectional"))
      (node (ref "R72") (pin "1") (pinfunction "1_1") (pintype "passive"))
      (node (ref "X10") (pin "4A") (pinfunction "2_4A") (pintype "passive"))
    )
    (net (code "71") (name "Net-(IC4-GPB1)") (class "Default")
      (node (ref "IC4") (pin "2") (pinfunction "GPB1_2") (pintype "bidirectional"))
      (node (ref "R71") (pin "1") (pinfunction "1_1") (pintype "passive"))
      (node (ref "X10") (pin "3A") (pinfunction "2_3A") (pintype "passive"))
    )
    (net (code "72") (name "Net-(IC4-GPB2)") (class "Default")
      (node (ref "IC4") (pin "3") (pinfunction "GPB2_3") (pintype "bidirectional"))
      (node (ref "R70") (pin "1") (pinfunction "1_1") (pintype "passive"))
      (node (ref "X10") (pin "2A") (pinfunction "2_2A") (pintype "passive"))
    )
    (net (code "73") (name "Net-(IC4-GPB3)") (class "Default")
      (node (ref "IC4") (pin "4") (pinfunction "GPB3_4") (pintype "bidirectional"))
      (node (ref "R69") (pin "1") (pinfunction "1_1") (pintype "passive"))
      (node (ref "X10") (pin "1A") (pinfunction "2_1A") (pintype "passive"))
    )
    (net (code "74") (name "Net-(IC4-GPB4)") (class "Default")
      (node (ref "IC4") (pin "5") (pinfunction "GPB4_5") (pintype "bidirectional"))
      (node (ref "R68") (pin "1") (pinfunction "1_1") (pintype "passive"))
      (node (ref "X11") (pin "4A") (pinfunction "2_4A") (pintype "passive"))
    )
    (net (code "75") (name "Net-(IC4-GPB5)") (class "Default")
      (node (ref "IC4") (pin "6") (pinfunction "GPB5_6") (pintype "bidirectional"))
      (node (ref "R67") (pin "1") (pinfunction "1_1") (pintype "passive"))
      (node (ref "X11") (pin "3A") (pinfunction "2_3A") (pintype "passive"))
    )
    (net (code "76") (name "Net-(IC4-GPB6)") (class "Default")
      (node (ref "IC4") (pin "7") (pinfunction "GPB6_7") (pintype "bidirectional"))
      (node (ref "R66") (pin "1") (pinfunction "1_1") (pintype "passive"))
      (node (ref "X11") (pin "2A") (pinfunction "2_2A") (pintype "passive"))
    )
    (net (code "77") (name "Net-(IC4-GPB7)") (class "Default")
      (node (ref "IC4") (pin "8") (pinfunction "GPB7_8") (pintype "bidirectional"))
      (node (ref "R65") (pin "1") (pinfunction "1_1") (pintype "passive"))
      (node (ref "X11") (pin "1A") (pinfunction "2_1A") (pintype "passive"))
    )
    (net (code "78") (name "Net-(IC4-INTA)") (class "Default")
      (node (ref "IC4") (pin "20") (pinfunction "INTA_20") (pintype "output"))
      (node (ref "X17") (pin "1A") (pinfunction "2_1A") (pintype "passive"))
    )
    (net (code "79") (name "Net-(IC4-INTB)") (class "Default")
      (node (ref "IC4") (pin "19") (pinfunction "INTB_19") (pintype "output"))
      (node (ref "X17") (pin "2A") (pinfunction "2_2A") (pintype "passive"))
    )
    (net (code "80") (name "Net-(IC4-~{RESET})") (class "Default")
      (node (ref "IC4") (pin "18") (pinfunction "~{RESET}_18") (pintype "input"))
      (node (ref "R55") (pin "2") (pinfunction "2_2") (pintype "passive"))
    )
    (net (code "81") (name "Net-(IC5-GPA0)") (class "Default")
      (node (ref "IC5") (pin "21") (pinfunction "GPA0_21") (pintype "bidirectional"))
      (node (ref "R75") (pin "2") (pinfunction "2_2") (pintype "passive"))
      (node (ref "X12") (pin "6A") (pinfunction "2_6A") (pintype "passive"))
    )
    (net (code "82") (name "Net-(IC5-GPA1)") (class "Default")
      (node (ref "IC5") (pin "22") (pinfunction "GPA1_22") (pintype "bidirectional"))
      (node (ref "R76") (pin "2") (pinfunction "2_2") (pintype "passive"))
      (node (ref "X12") (pin "5A") (pinfunction "2_5A") (pintype "passive"))
    )
    (net (code "83") (name "Net-(IC5-GPA2)") (class "Default")
      (node (ref "IC5") (pin "23") (pinfunction "GPA2_23") (pintype "bidirectional"))
      (node (ref "R77") (pin "2") (pinfunction "2_2") (pintype "passive"))
      (node (ref "X12") (pin "4A") (pinfunction "2_4A") (pintype "passive"))
    )
    (net (code "84") (name "Net-(IC5-GPA3)") (class "Default")
      (node (ref "IC5") (pin "24") (pinfunction "GPA3_24") (pintype "bidirectional"))
      (node (ref "R78") (pin "2") (pinfunction "2_2") (pintype "passive"))
      (node (ref "X12") (pin "3A") (pinfunction "2_3A") (pintype "passive"))
    )
    (net (code "85") (name "Net-(IC5-GPA4)") (class "Default")
      (node (ref "IC5") (pin "25") (pinfunction "GPA4_25") (pintype "bidirectional"))
      (node (ref "R79") (pin "2") (pinfunction "2_2") (pintype "passive"))
      (node (ref "X12") (pin "2A") (pinfunction "2_2A") (pintype "passive"))
    )
    (net (code "86") (name "Net-(IC5-GPA5)") (class "Default")
      (node (ref "IC5") (pin "26") (pinfunction "GPA5_26") (pintype "bidirectional"))
      (node (ref "R80") (pin "2") (pinfunction "2_2") (pintype "passive"))
      (node (ref "X12") (pin "1A") (pinfunction "2_1A") (pintype "passive"))
    )
    (net (code "87") (name "Net-(IC5-GPA6)") (class "Default")
      (node (ref "IC5") (pin "27") (pinfunction "GPA6_27") (pintype "bidirectional"))
      (node (ref "R81") (pin "2") (pinfunction "2_2") (pintype "passive"))
      (node (ref "X13") (pin "6A") (pinfunction "2_6A") (pintype "passive"))
    )
    (net (code "88") (name "Net-(IC5-GPA7)") (class "Default")
      (node (ref "IC5") (pin "28") (pinfunction "GPA7_28") (pintype "bidirectional"))
      (node (ref "R82") (pin "2") (pinfunction "2_2") (pintype "passive"))
      (node (ref "X13") (pin "5A") (pinfunction "2_5A") (pintype "passive"))
    )
    (net (code "89") (name "Net-(IC5-GPB0)") (class "Default")
      (node (ref "IC5") (pin "1") (pinfunction "GPB0_1") (pintype "bidirectional"))
      (node (ref "R90") (pin "1") (pinfunction "1_1") (pintype "passive"))
      (node (ref "X13") (pin "4A") (pinfunction "2_4A") (pintype "passive"))
    )
    (net (code "90") (name "Net-(IC5-GPB1)") (class "Default")
      (node (ref "IC5") (pin "2") (pinfunction "GPB1_2") (pintype "bidirectional"))
      (node (ref "R89") (pin "1") (pinfunction "1_1") (pintype "passive"))
      (node (ref "X13") (pin "3A") (pinfunction "2_3A") (pintype "passive"))
    )
    (net (code "91") (name "Net-(IC5-GPB2)") (class "Default")
      (node (ref "IC5") (pin "3") (pinfunction "GPB2_3") (pintype "bidirectional"))
      (node (ref "R88") (pin "1") (pinfunction "1_1") (pintype "passive"))
      (node (ref "X13") (pin "2A") (pinfunction "2_2A") (pintype "passive"))
    )
    (net (code "92") (name "Net-(IC5-GPB3)") (class "Default")
      (node (ref "IC5") (pin "4") (pinfunction "GPB3_4") (pintype "bidirectional"))
      (node (ref "R87") (pin "1") (pinfunction "1_1") (pintype "passive"))
      (node (ref "X13") (pin "1A") (pinfunction "2_1A") (pintype "passive"))
    )
    (net (code "93") (name "Net-(IC5-GPB4)") (class "Default")
      (node (ref "IC5") (pin "5") (pinfunction "GPB4_5") (pintype "bidirectional"))
      (node (ref "R86") (pin "1") (pinfunction "1_1") (pintype "passive"))
      (node (ref "X14") (pin "4A") (pinfunction "2_4A") (pintype "passive"))
    )
    (net (code "94") (name "Net-(IC5-GPB5)") (class "Default")
      (node (ref "IC5") (pin "6") (pinfunction "GPB5_6") (pintype "bidirectional"))
      (node (ref "R85") (pin "1") (pinfunction "1_1") (pintype "passive"))
      (node (ref "X14") (pin "3A") (pinfunction "2_3A") (pintype "passive"))
    )
    (net (code "95") (name "Net-(IC5-GPB6)") (class "Default")
      (node (ref "IC5") (pin "7") (pinfunction "GPB6_7") (pintype "bidirectional"))
      (node (ref "R84") (pin "1") (pinfunction "1_1") (pintype "passive"))
      (node (ref "X14") (pin "2A") (pinfunction "2_2A") (pintype "passive"))
    )
    (net (code "96") (name "Net-(IC5-GPB7)") (class "Default")
      (node (ref "IC5") (pin "8") (pinfunction "GPB7_8") (pintype "bidirectional"))
      (node (ref "R83") (pin "1") (pinfunction "1_1") (pintype "passive"))
      (node (ref "X14") (pin "1A") (pinfunction "2_1A") (pintype "passive"))
    )
    (net (code "97") (name "Net-(IC5-INTA)") (class "Default")
      (node (ref "IC5") (pin "20") (pinfunction "INTA_20") (pintype "output"))
      (node (ref "X18") (pin "1A") (pinfunction "2_1A") (pintype "passive"))
    )
    (net (code "98") (name "Net-(IC5-INTB)") (class "Default")
      (node (ref "IC5") (pin "19") (pinfunction "INTB_19") (pintype "output"))
      (node (ref "X18") (pin "2A") (pinfunction "2_2A") (pintype "passive"))
    )
    (net (code "99") (name "Net-(IC5-~{RESET})") (class "Default")
      (node (ref "IC5") (pin "18") (pinfunction "~{RESET}_18") (pintype "input"))
      (node (ref "R73") (pin "2") (pinfunction "2_2") (pintype "passive"))
    )
    (net (code "100") (name "unconnected-(X1-Pad1)") (class "Default")
      (node (ref "X1") (pin "1") (pinfunction "1_1") (pintype "passive"))
    )
    (net (code "101") (name "unconnected-(X1B-1-Pad2)") (class "Default")
      (node (ref "X1") (pin "2") (pinfunction "1_2") (pintype "passive"))
    )
    (net (code "102") (name "unconnected-(X1C-1-Pad3)") (class "Default")
      (node (ref "X1") (pin "3") (pinfunction "1_3") (pintype "passive"))
    )
    (net (code "103") (name "unconnected-(X1D-1-Pad4)") (class "Default")
      (node (ref "X1") (pin "4") (pinfunction "1_4") (pintype "passive"))
    )
    (net (code "104") (name "unconnected-(X1E-1-Pad5)") (class "Default")
      (node (ref "X1") (pin "5") (pinfunction "1_5") (pintype "passive"))
    )
    (net (code "105") (name "unconnected-(X1F-1-Pad6)") (class "Default")
      (node (ref "X1") (pin "6") (pinfunction "1_6") (pintype "passive"))
    )
    (net (code "106") (name "unconnected-(X2-Pad1)") (class "Default")
      (node (ref "X2") (pin "1") (pinfunction "1_1") (pintype "passive"))
    )
    (net (code "107") (name "unconnected-(X2B-1-Pad2)") (class "Default")
      (node (ref "X2") (pin "2") (pinfunction "1_2") (pintype "passive"))
    )
    (net (code "108") (name "unconnected-(X2C-1-Pad3)") (class "Default")
      (node (ref "X2") (pin "3") (pinfunction "1_3") (pintype "passive"))
    )
    (net (code "109") (name "unconnected-(X2D-1-Pad4)") (class "Default")
      (node (ref "X2") (pin "4") (pinfunction "1_4") (pintype "passive"))
    )
    (net (code "110") (name "unconnected-(X2E-1-Pad5)") (class "Default")
      (node (ref "X2") (pin "5") (pinfunction "1_5") (pintype "passive"))
    )
    (net (code "111") (name "unconnected-(X2F-1-Pad6)") (class "Default")
      (node (ref "X2") (pin "6") (pinfunction "1_6") (pintype "passive"))
    )
    (net (code "112") (name "unconnected-(X3-Pad1)") (class "Default")
      (node (ref "X3") (pin "1") (pinfunction "1_1") (pintype "passive"))
    )
    (net (code "113") (name "unconnected-(X3B-1-Pad2)") (class "Default")
      (node (ref "X3") (pin "2") (pinfunction "1_2") (pintype "passive"))
    )
    (net (code "114") (name "unconnected-(X3C-1-Pad3)") (class "Default")
      (node (ref "X3") (pin "3") (pinfunction "1_3") (pintype "passive"))
    )
    (net (code "115") (name "unconnected-(X3D-1-Pad4)") (class "Default")
      (node (ref "X3") (pin "4") (pinfunction "1_4") (pintype "passive"))
    )
    (net (code "116") (name "unconnected-(X4-Pad1)") (class "Default")
      (node (ref "X4") (pin "1") (pinfunction "1_1") (pintype "passive"))
    )
    (net (code "117") (name "unconnected-(X4B-1-Pad2)") (class "Default")
      (node (ref "X4") (pin "2") (pinfunction "1_2") (pintype "passive"))
    )
    (net (code "118") (name "unconnected-(X4C-1-Pad3)") (class "Default")
      (node (ref "X4") (pin "3") (pinfunction "1_3") (pintype "passive"))
    )
    (net (code "119") (name "unconnected-(X4D-1-Pad4)") (class "Default")
      (node (ref "X4") (pin "4") (pinfunction "1_4") (pintype "passive"))
    )
    (net (code "120") (name "unconnected-(X4E-1-Pad5)") (class "Default")
      (node (ref "X4") (pin "5") (pinfunction "1_5") (pintype "passive"))
    )
    (net (code "121") (name "unconnected-(X4F-1-Pad6)") (class "Default")
      (node (ref "X4") (pin "6") (pinfunction "1_6") (pintype "passive"))
    )
    (net (code "122") (name "unconnected-(X5-Pad1)") (class "Default")
      (node (ref "X5") (pin "1") (pinfunction "1_1") (pintype "passive"))
    )
    (net (code "123") (name "unconnected-(X5B-1-Pad2)") (class "Default")
      (node (ref "X5") (pin "2") (pinfunction "1_2") (pintype "passive"))
    )
    (net (code "124") (name "unconnected-(X5C-1-Pad3)") (class "Default")
      (node (ref "X5") (pin "3") (pinfunction "1_3") (pintype "passive"))
    )
    (net (code "125") (name "unconnected-(X5D-1-Pad4)") (class "Default")
      (node (ref "X5") (pin "4") (pinfunction "1_4") (pintype "passive"))
    )
    (net (code "126") (name "unconnected-(X5E-1-Pad5)") (class "Default")
      (node (ref "X5") (pin "5") (pinfunction "1_5") (pintype "passive"))
    )
    (net (code "127") (name "unconnected-(X5F-1-Pad6)") (class "Default")
      (node (ref "X5") (pin "6") (pinfunction "1_6") (pintype "passive"))
    )
    (net (code "128") (name "unconnected-(X6-Pad1)") (class "Default")
      (node (ref "X6") (pin "1") (pinfunction "1_1") (pintype "passive"))
    )
    (net (code "129") (name "unconnected-(X6B-1-Pad2)") (class "Default")
      (node (ref "X6") (pin "2") (pinfunction "1_2") (pintype "passive"))
    )
    (net (code "130") (name "unconnected-(X6C-1-Pad3)") (class "Default")
      (node (ref "X6") (pin "3") (pinfunction "1_3") (pintype "passive"))
    )
    (net (code "131") (name "unconnected-(X6D-1-Pad4)") (class "Default")
      (node (ref "X6") (pin "4") (pinfunction "1_4") (pintype "passive"))
    )
    (net (code "132") (name "unconnected-(X6E-1-Pad5)") (class "Default")
      (node (ref "X6") (pin "5") (pinfunction "1_5") (pintype "passive"))
    )
    (net (code "133") (name "unconnected-(X6F-1-Pad6)") (class "Default")
      (node (ref "X6") (pin "6") (pinfunction "1_6") (pintype "passive"))
    )
    (net (code "134") (name "unconnected-(X7-Pad1)") (class "Default")
      (node (ref "X7") (pin "1") (pinfunction "1_1") (pintype "passive"))
    )
    (net (code "135") (name "unconnected-(X7B-1-Pad2)") (class "Default")
      (node (ref "X7") (pin "2") (pinfunction "1_2") (pintype "passive"))
    )
    (net (code "136") (name "unconnected-(X7C-1-Pad3)") (class "Default")
      (node (ref "X7") (pin "3") (pinfunction "1_3") (pintype "passive"))
    )
    (net (code "137") (name "unconnected-(X7D-1-Pad4)") (class "Default")
      (node (ref "X7") (pin "4") (pinfunction "1_4") (pintype "passive"))
    )
    (net (code "138") (name "unconnected-(X7E-1-Pad5)") (class "Default")
      (node (ref "X7") (pin "5") (pinfunction "1_5") (pintype "passive"))
    )
    (net (code "139") (name "unconnected-(X7F-1-Pad6)") (class "Default")
      (node (ref "X7") (pin "6") (pinfunction "1_6") (pintype "passive"))
    )
    (net (code "140") (name "unconnected-(X8-Pad1)") (class "Default")
      (node (ref "X8") (pin "1") (pinfunction "1_1") (pintype "passive"))
    )
    (net (code "141") (name "unconnected-(X8B-1-Pad2)") (class "Default")
      (node (ref "X8") (pin "2") (pinfunction "1_2") (pintype "passive"))
    )
    (net (code "142") (name "unconnected-(X8C-1-Pad3)") (class "Default")
      (node (ref "X8") (pin "3") (pinfunction "1_3") (pintype "passive"))
    )
    (net (code "143") (name "unconnected-(X8D-1-Pad4)") (class "Default")
      (node (ref "X8") (pin "4") (pinfunction "1_4") (pintype "passive"))
    )
    (net (code "144") (name "unconnected-(X9-Pad1)") (class "Default")
      (node (ref "X9") (pin "1") (pinfunction "1_1") (pintype "passive"))
    )
    (net (code "145") (name "unconnected-(X9B-1-Pad2)") (class "Default")
      (node (ref "X9") (pin "2") (pinfunction "1_2") (pintype "passive"))
    )
    (net (code "146") (name "unconnected-(X9C-1-Pad3)") (class "Default")
      (node (ref "X9") (pin "3") (pinfunction "1_3") (pintype "passive"))
    )
    (net (code "147") (name "unconnected-(X9D-1-Pad4)") (class "Default")
      (node (ref "X9") (pin "4") (pinfunction "1_4") (pintype "passive"))
    )
    (net (code "148") (name "unconnected-(X9E-1-Pad5)") (class "Default")
      (node (ref "X9") (pin "5") (pinfunction "1_5") (pintype "passive"))
    )
    (net (code "149") (name "unconnected-(X9F-1-Pad6)") (class "Default")
      (node (ref "X9") (pin "6") (pinfunction "1_6") (pintype "passive"))
    )
    (net (code "150") (name "unconnected-(X10-Pad1)") (class "Default")
      (node (ref "X10") (pin "1") (pinfunction "1_1") (pintype "passive"))
    )
    (net (code "151") (name "unconnected-(X10B-1-Pad2)") (class "Default")
      (node (ref "X10") (pin "2") (pinfunction "1_2") (pintype "passive"))
    )
    (net (code "152") (name "unconnected-(X10C-1-Pad3)") (class "Default")
      (node (ref "X10") (pin "3") (pinfunction "1_3") (pintype "passive"))
    )
    (net (code "153") (name "unconnected-(X10D-1-Pad4)") (class "Default")
      (node (ref "X10") (pin "4") (pinfunction "1_4") (pintype "passive"))
    )
    (net (code "154") (name "unconnected-(X10E-1-Pad5)") (class "Default")
      (node (ref "X10") (pin "5") (pinfunction "1_5") (pintype "passive"))
    )
    (net (code "155") (name "unconnected-(X10F-1-Pad6)") (class "Default")
      (node (ref "X10") (pin "6") (pinfunction "1_6") (pintype "passive"))
    )
    (net (code "156") (name "unconnected-(X11-Pad1)") (class "Default")
      (node (ref "X11") (pin "1") (pinfunction "1_1") (pintype "passive"))
    )
    (net (code "157") (name "unconnected-(X11B-1-Pad2)") (class "Default")
      (node (ref "X11") (pin "2") (pinfunction "1_2") (pintype "passive"))
    )
    (net (code "158") (name "unconnected-(X11C-1-Pad3)") (class "Default")
      (node (ref "X11") (pin "3") (pinfunction "1_3") (pintype "passive"))
    )
    (net (code "159") (name "unconnected-(X11D-1-Pad4)") (class "Default")
      (node (ref "X11") (pin "4") (pinfunction "1_4") (pintype "passive"))
    )
    (net (code "160") (name "unconnected-(X12-Pad1)") (class "Default")
      (node (ref "X12") (pin "1") (pinfunction "1_1") (pintype "passive"))
    )
    (net (code "161") (name "unconnected-(X12B-1-Pad2)") (class "Default")
      (node (ref "X12") (pin "2") (pinfunction "1_2") (pintype "passive"))
    )
    (net (code "162") (name "unconnected-(X12C-1-Pad3)") (class "Default")
      (node (ref "X12") (pin "3") (pinfunction "1_3") (pintype "passive"))
    )
    (net (code "163") (name "unconnected-(X12D-1-Pad4)") (class "Default")
      (node (ref "X12") (pin "4") (pinfunction "1_4") (pintype "passive"))
    )
    (net (code "164") (name "unconnected-(X12E-1-Pad5)") (class "Default")
      (node (ref "X12") (pin "5") (pinfunction "1_5") (pintype "passive"))
    )
    (net (code "165") (name "unconnected-(X12F-1-Pad6)") (class "Default")
      (node (ref "X12") (pin "6") (pinfunction "1_6") (pintype "passive"))
    )
    (net (code "166") (name "unconnected-(X13-Pad1)") (class "Default")
      (node (ref "X13") (pin "1") (pinfunction "1_1") (pintype "passive"))
    )
    (net (code "167") (name "unconnected-(X13B-1-Pad2)") (class "Default")
      (node (ref "X13") (pin "2") (pinfunction "1_2") (pintype "passive"))
    )
    (net (code "168") (name "unconnected-(X13C-1-Pad3)") (class "Default")
      (node (ref "X13") (pin "3") (pinfunction "1_3") (pintype "passive"))
    )
    (net (code "169") (name "unconnected-(X13D-1-Pad4)") (class "Default")
      (node (ref "X13") (pin "4") (pinfunction "1_4") (pintype "passive"))
    )
    (net (code "170") (name "unconnected-(X13E-1-Pad5)") (class "Default")
      (node (ref "X13") (pin "5") (pinfunction "1_5") (pintype "passive"))
    )
    (net (code "171") (name "unconnected-(X13F-1-Pad6)") (class "Default")
      (node (ref "X13") (pin "6") (pinfunction "1_6") (pintype "passive"))
    )
    (net (code "172") (name "unconnected-(X14-Pad1)") (class "Default")
      (node (ref "X14") (pin "1") (pinfunction "1_1") (pintype "passive"))
    )
    (net (code "173") (name "unconnected-(X14B-1-Pad2)") (class "Default")
      (node (ref "X14") (pin "2") (pinfunction "1_2") (pintype "passive"))
    )
    (net (code "174") (name "unconnected-(X14C-1-Pad3)") (class "Default")
      (node (ref "X14") (pin "3") (pinfunction "1_3") (pintype "passive"))
    )
    (net (code "175") (name "unconnected-(X14D-1-Pad4)") (class "Default")
      (node (ref "X14") (pin "4") (pinfunction "1_4") (pintype "passive"))
    )
    (net (code "176") (name "unconnected-(X15-Pad1)") (class "Default")
      (node (ref "X15") (pin "1") (pinfunction "1_1") (pintype "passive"))
    )
    (net (code "177") (name "unconnected-(X15B-1-Pad2)") (class "Default")
      (node (ref "X15") (pin "2") (pinfunction "1_2") (pintype "passive"))
    )
    (net (code "178") (name "unconnected-(X16-Pad1)") (class "Default")
      (node (ref "X16") (pin "1") (pinfunction "1_1") (pintype "passive"))
    )
    (net (code "179") (name "unconnected-(X16B-1-Pad2)") (class "Default")
      (node (ref "X16") (pin "2") (pinfunction "1_2") (pintype "passive"))
    )
    (net (code "180") (name "unconnected-(X17-Pad1)") (class "Default")
      (node (ref "X17") (pin "1") (pinfunction "1_1") (pintype "passive"))
    )
    (net (code "181") (name "unconnected-(X17B-1-Pad2)") (class "Default")
      (node (ref "X17") (pin "2") (pinfunction "1_2") (pintype "passive"))
    )
    (net (code "182") (name "unconnected-(X18-Pad1)") (class "Default")
      (node (ref "X18") (pin "1") (pinfunction "1_1") (pintype "passive"))
    )
    (net (code "183") (name "unconnected-(X18B-1-Pad2)") (class "Default")
      (node (ref "X18") (pin "2") (pinfunction "1_2") (pintype "passive"))
    )
    (net (code "184") (name "unconnected-(X47-Pad1)") (class "Default")
      (node (ref "X47") (pin "1") (pinfunction "1_1") (pintype "passive"))
    )
    (net (code "185") (name "unconnected-(X47B-1-Pad2)") (class "Default")
      (node (ref "X47") (pin "2") (pinfunction "1_2") (pintype "passive"))
    )
    (net (code "186") (name "unconnected-(X47C-1-Pad3)") (class "Default")
      (node (ref "X47") (pin "3") (pinfunction "1_3") (pintype "passive"))
    )
    (net (code "187") (name "unconnected-(X47D-1-Pad4)") (class "Default")
      (node (ref "X47") (pin "4") (pinfunction "1_4") (pintype "passive"))
    )
    (net (code "188") (name "unconnected-(X51-Pad1)") (class "Default")
      (node (ref "X51") (pin "1") (pinfunction "1_1") (pintype "passive"))
    )
    (net (code "189") (name "unconnected-(X51B-1-Pad2)") (class "Default")
      (node (ref "X51") (pin "2") (pinfunction "1_2") (pintype "passive"))
    )
    (net (code "190") (name "unconnected-(X52-Pad1)") (class "Default")
      (node (ref "X52") (pin "1") (pinfunction "1_1") (pintype "passive"))
    )
    (net (code "191") (name "unconnected-(X52B-1-Pad2)") (class "Default")
      (node (ref "X52") (pin "2") (pinfunction "1_2") (pintype "passive"))
    )
    (net (code "192") (name "unconnected-(X53-Pad1)") (class "Default")
      (node (ref "X53") (pin "1") (pinfunction "1_1") (pintype "passive"))
    )
    (net (code "193") (name "unconnected-(X53B-1-Pad2)") (class "Default")
      (node (ref "X53") (pin "2") (pinfunction "1_2") (pintype "passive"))
    )
  )
)
